# eink_schematic.net
KiCad netlist of a schematic drawn in EAGLE
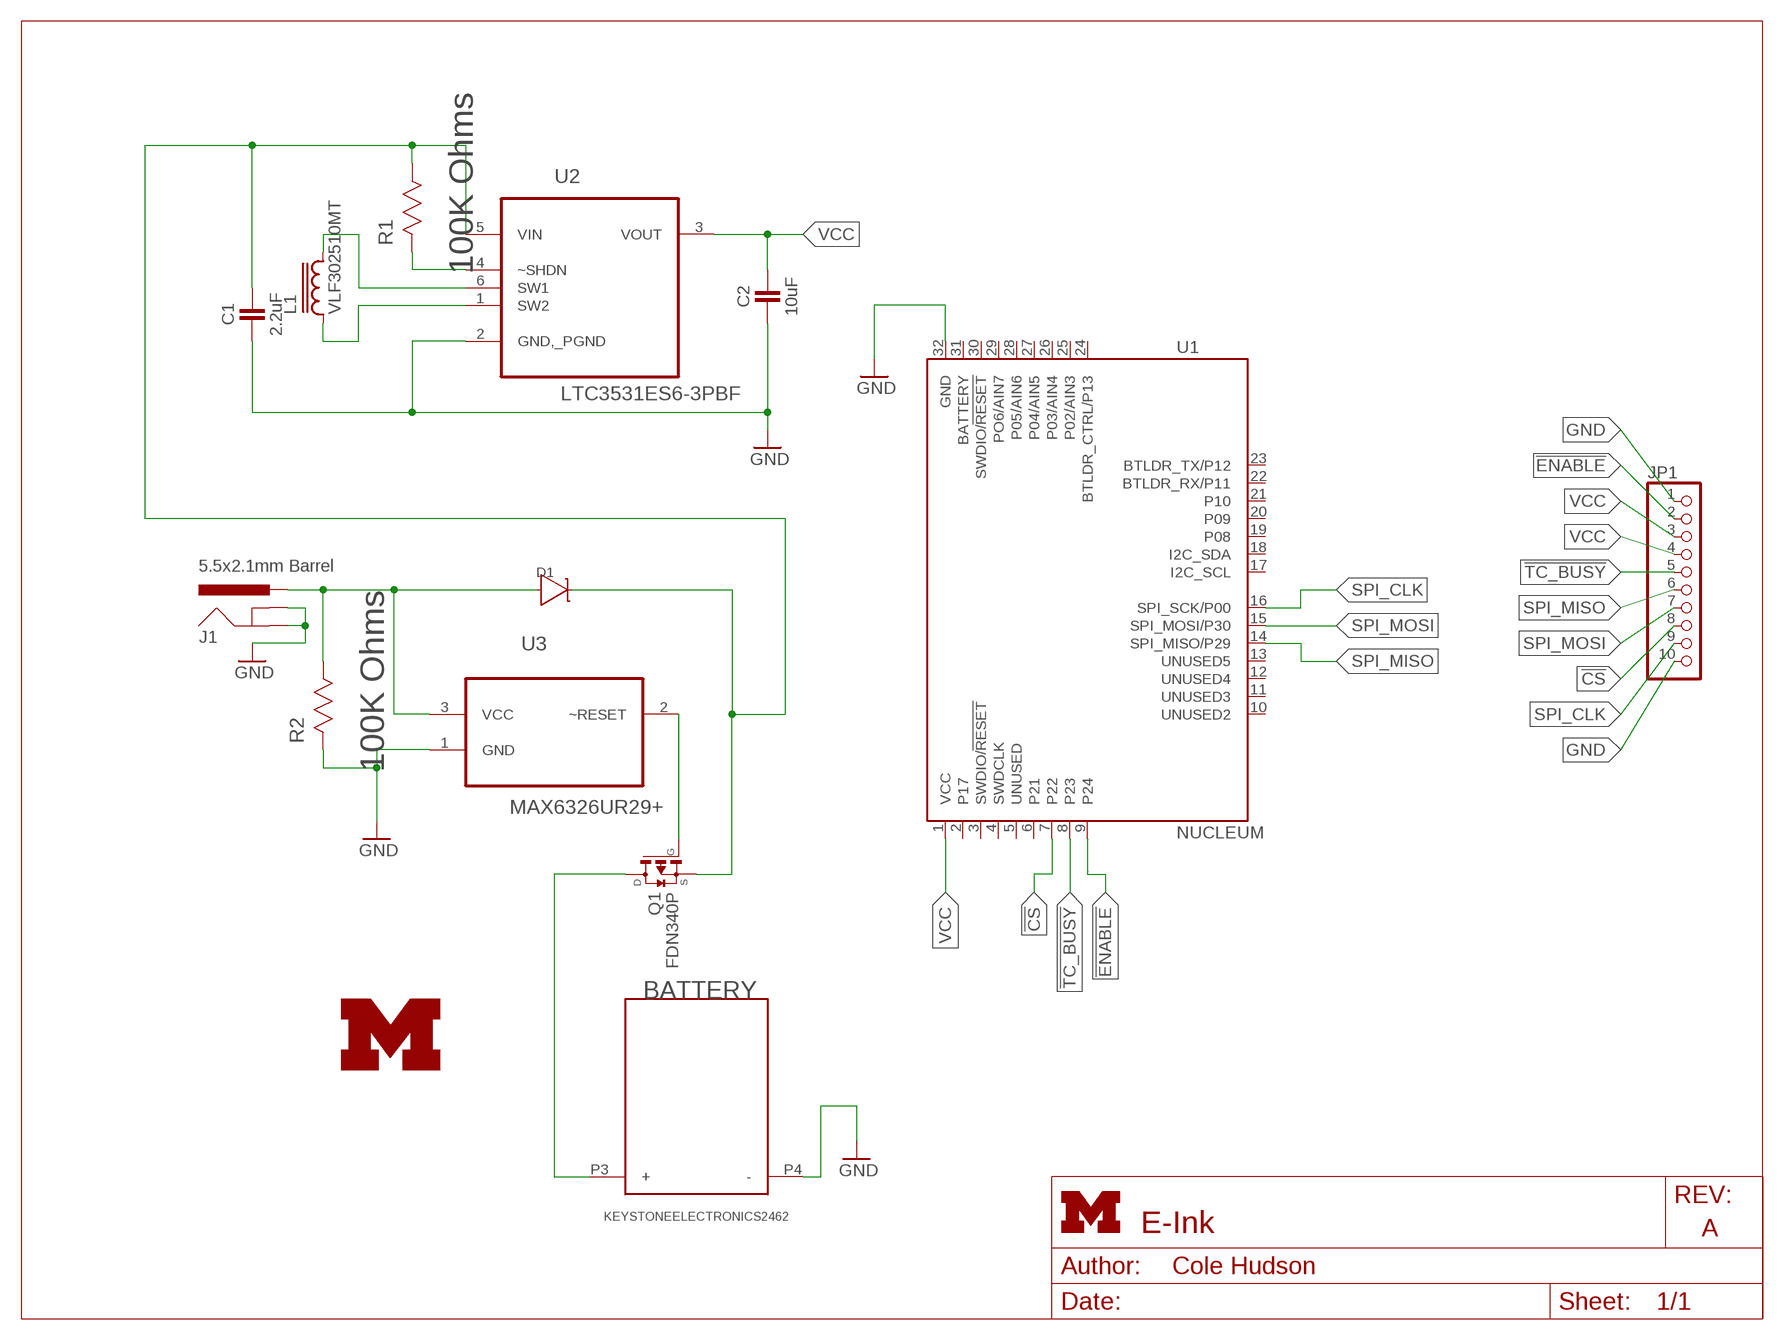
[diagram p0: schematic, sheet 1]

(export (version "E")
  (design (tool "Eeschema 10.0.6"))
  (components
    (comp (ref "BATTERY")
      (value "KEYSTONEELECTRONICS2462")
      (footprint "eagle-import:KEYSTONEELECTRONICS2462")
      (libsource (lib "eagle-import") (part "KEYSTONEELECTRONICS2462"))
    )
    (comp (ref "C1")
      (value "2.2uF")
      (footprint "eagle-import:0402_CAP")
      (libsource (lib "eagle-import") (part "CAPACITOR"))
    )
    (comp (ref "C2")
      (value "10uF")
      (footprint "eagle-import:0402_CAP")
      (libsource (lib "eagle-import") (part "CAPACITOR"))
    )
    (comp (ref "D1")
      (value "DIODE[SCHOTKY]-SOD123W")
      (footprint "eagle-import:SOD123W")
      (libsource (lib "eagle-import") (part "DIODE[SCHOTKY]-SOD123W"))
    )
    (comp (ref "J1")
      (value "5.5x2.1mm Barrel")
      (footprint "eagle-import:POWER_JACK_SMD")
      (libsource (lib "eagle-import") (part "POWER_JACKSMD"))
    )
    (comp (ref "JP1")
      (value "PINHD-1X10/90")
      (footprint "eagle-import:1X10_90")
      (libsource (lib "eagle-import") (part "PINHD-1X10/90"))
    )
    (comp (ref "L1")
      (value "VLF302510MT")
      (footprint "eagle-import:VLF302510MT")
      (libsource (lib "eagle-import") (part "VLF302510MT"))
    )
    (comp (ref "LOGO1")
      (value "UMICH_SOLID_LARGE")
      (footprint "eagle-import:UMICH_SOLID_350MIL")
      (libsource (lib "eagle-import") (part "UMICH_SOLID_LARGE"))
    )
    (comp (ref "Q1")
      (value "FDN340P")
      (footprint "eagle-import:SSOT-3")
      (libsource (lib "eagle-import") (part "FDN340P"))
    )
    (comp (ref "R1")
      (value "100K Ohms")
      (footprint "eagle-import:RESC1608X60N")
      (fields (field (name "MPN") "RC0603JR-07100KL") (field (name "TOLERANCE") "±5%"))
      (libsource (lib "eagle-import") (part "RC0603JR-07100KL"))
    )
    (comp (ref "R2")
      (value "100K Ohms")
      (footprint "eagle-import:RESC1608X60N")
      (fields (field (name "MPN") "RC0603JR-07100KL") (field (name "TOLERANCE") "±5%"))
      (libsource (lib "eagle-import") (part "RC0603JR-07100KL"))
    )
    (comp (ref "U1")
      (value "NUCLEUM")
      (footprint "eagle-import:NUCLEUM")
      (libsource (lib "eagle-import") (part "NUCLEUM"))
    )
    (comp (ref "U2")
      (value "LTC3531ES6-3PBF")
      (footprint "eagle-import:SOT95P280X100-6N")
      (fields (field (name "MPN") "LTC3531ES6-3#PBF"))
      (libsource (lib "eagle-import") (part "LTC3531ES6-3PBF"))
    )
    (comp (ref "U3")
      (value "MAX6326UR29+")
      (footprint "eagle-import:SOT95P228X119-3N")
      (libsource (lib "eagle-import") (part "MAX6326UR29+"))
    )
  )
  (nets
    (net (code "1") (name "/~{CS}") (class "Default")
      (node (ref "JP1") (pin "8") (pinfunction "8_8") (pintype "passive"))
      (node (ref "U1") (pin "7") (pinfunction "P22_7") (pintype "bidirectional"))
    )
    (net (code "2") (name "/~{ENABLE}") (class "Default")
      (node (ref "JP1") (pin "2") (pinfunction "2_2") (pintype "passive"))
      (node (ref "U1") (pin "9") (pinfunction "P24_9") (pintype "bidirectional"))
    )
    (net (code "3") (name "/~{TC_BUSY}") (class "Default")
      (node (ref "JP1") (pin "5") (pinfunction "5_5") (pintype "passive"))
      (node (ref "U1") (pin "8") (pinfunction "P23_8") (pintype "bidirectional"))
    )
    (net (code "4") (name "GND") (class "Default")
      (node (ref "BATTERY") (pin "P4") (pinfunction "-_P4") (pintype "bidirectional"))
      (node (ref "C1") (pin "2") (pinfunction "2_2") (pintype "bidirectional"))
      (node (ref "C2") (pin "2") (pinfunction "2_2") (pintype "bidirectional"))
      (node (ref "J1") (pin "GND") (pinfunction "GNDBREAK_GND") (pintype "bidirectional"))
      (node (ref "J1") (pin "P$4") (pinfunction "GND_P$4") (pintype "bidirectional"))
      (node (ref "JP1") (pin "1") (pinfunction "1_1") (pintype "passive"))
      (node (ref "JP1") (pin "10") (pinfunction "10_10") (pintype "passive"))
      (node (ref "R2") (pin "2") (pinfunction "R2_2") (pintype "passive"))
      (node (ref "U1") (pin "32") (pinfunction "GND_32") (pintype "bidirectional"))
      (node (ref "U2") (pin "2") (pinfunction "GND,_PGND_2") (pintype "passive"))
      (node (ref "U3") (pin "1") (pinfunction "GND_1") (pintype "passive"))
    )
    (net (code "5") (name "Net-(BATTERY-+)") (class "Default")
      (node (ref "BATTERY") (pin "P3") (pinfunction "+_P3") (pintype "bidirectional"))
      (node (ref "Q1") (pin "3") (pinfunction "D_3") (pintype "passive"))
    )
    (net (code "6") (name "Net-(D1-1)") (class "Default")
      (node (ref "D1") (pin "P$1") (pinfunction "1_P$1") (pintype "bidirectional"))
      (node (ref "J1") (pin "VIN0") (pinfunction "PWR_VIN0") (pintype "bidirectional"))
      (node (ref "R2") (pin "1") (pinfunction "R1_1") (pintype "passive"))
      (node (ref "U3") (pin "3") (pinfunction "VCC_3") (pintype "power_in"))
    )
    (net (code "7") (name "Net-(D1-2)") (class "Default")
      (node (ref "C1") (pin "1") (pinfunction "1_1") (pintype "bidirectional"))
      (node (ref "D1") (pin "P$2") (pinfunction "2_P$2") (pintype "bidirectional"))
      (node (ref "Q1") (pin "2") (pinfunction "S_2") (pintype "passive"))
      (node (ref "R1") (pin "1") (pinfunction "R1_1") (pintype "passive"))
      (node (ref "U2") (pin "5") (pinfunction "VIN_5") (pintype "power_in"))
    )
    (net (code "8") (name "Net-(Q1-G)") (class "Default")
      (node (ref "Q1") (pin "1") (pinfunction "G_1") (pintype "passive"))
      (node (ref "U3") (pin "2") (pinfunction "~{RESET}_2") (pintype "output"))
    )
    (net (code "9") (name "Net-(R1-R2)") (class "Default")
      (node (ref "R1") (pin "2") (pinfunction "R2_2") (pintype "passive"))
      (node (ref "U2") (pin "4") (pinfunction "~{SHDN}_4") (pintype "input"))
    )
    (net (code "10") (name "Net-(U2-SW1)") (class "Default")
      (node (ref "L1") (pin "2") (pinfunction "2_2") (pintype "passive"))
      (node (ref "U2") (pin "6") (pinfunction "SW1_6") (pintype "passive"))
    )
    (net (code "11") (name "Net-(U2-SW2)") (class "Default")
      (node (ref "L1") (pin "1") (pinfunction "1_1") (pintype "passive"))
      (node (ref "U2") (pin "1") (pinfunction "SW2_1") (pintype "passive"))
    )
    (net (code "12") (name "SPI_CLK") (class "Default")
      (node (ref "JP1") (pin "9") (pinfunction "9_9") (pintype "passive"))
      (node (ref "U1") (pin "16") (pinfunction "SPI_SCK/P00_16") (pintype "bidirectional"))
    )
    (net (code "13") (name "SPI_MISO") (class "Default")
      (node (ref "JP1") (pin "6") (pinfunction "6_6") (pintype "passive"))
      (node (ref "U1") (pin "14") (pinfunction "SPI_MISO/P29_14") (pintype "bidirectional"))
    )
    (net (code "14") (name "SPI_MOSI") (class "Default")
      (node (ref "JP1") (pin "7") (pinfunction "7_7") (pintype "passive"))
      (node (ref "U1") (pin "15") (pinfunction "SPI_MOSI/P30_15") (pintype "bidirectional"))
    )
    (net (code "15") (name "VCC") (class "Default")
      (node (ref "C2") (pin "1") (pinfunction "1_1") (pintype "bidirectional"))
      (node (ref "JP1") (pin "3") (pinfunction "3_3") (pintype "passive"))
      (node (ref "JP1") (pin "4") (pinfunction "4_4") (pintype "passive"))
      (node (ref "U1") (pin "1") (pinfunction "VCC_1") (pintype "bidirectional"))
      (node (ref "U2") (pin "3") (pinfunction "VOUT_3") (pintype "output"))
    )
    (net (code "16") (name "unconnected-(U1-BATTERY-Pad31)") (class "Default")
      (node (ref "U1") (pin "31") (pinfunction "BATTERY_31") (pintype "bidirectional"))
    )
    (net (code "17") (name "unconnected-(U1-BTLDR_CTRL{slash}P13-Pad24)") (class "Default")
      (node (ref "U1") (pin "24") (pinfunction "BTLDR_CTRL/P13_24") (pintype "bidirectional"))
    )
    (net (code "18") (name "unconnected-(U1-BTLDR_RX{slash}P11-Pad22)") (class "Default")
      (node (ref "U1") (pin "22") (pinfunction "BTLDR_RX/P11_22") (pintype "bidirectional"))
    )
    (net (code "19") (name "unconnected-(U1-BTLDR_TX{slash}P12-Pad23)") (class "Default")
      (node (ref "U1") (pin "23") (pinfunction "BTLDR_TX/P12_23") (pintype "bidirectional"))
    )
    (net (code "20") (name "unconnected-(U1-I2C_SCL-Pad17)") (class "Default")
      (node (ref "U1") (pin "17") (pinfunction "I2C_SCL_17") (pintype "bidirectional"))
    )
    (net (code "21") (name "unconnected-(U1-I2C_SDA-Pad18)") (class "Default")
      (node (ref "U1") (pin "18") (pinfunction "I2C_SDA_18") (pintype "bidirectional"))
    )
    (net (code "22") (name "unconnected-(U1-P02{slash}AIN3-Pad25)") (class "Default")
      (node (ref "U1") (pin "25") (pinfunction "P02/AIN3_25") (pintype "bidirectional"))
    )
    (net (code "23") (name "unconnected-(U1-P03{slash}AIN4-Pad26)") (class "Default")
      (node (ref "U1") (pin "26") (pinfunction "P03/AIN4_26") (pintype "bidirectional"))
    )
    (net (code "24") (name "unconnected-(U1-P04{slash}AIN5-Pad27)") (class "Default")
      (node (ref "U1") (pin "27") (pinfunction "P04/AIN5_27") (pintype "bidirectional"))
    )
    (net (code "25") (name "unconnected-(U1-P05{slash}AIN6-Pad28)") (class "Default")
      (node (ref "U1") (pin "28") (pinfunction "P05/AIN6_28") (pintype "bidirectional"))
    )
    (net (code "26") (name "unconnected-(U1-P08-Pad19)") (class "Default")
      (node (ref "U1") (pin "19") (pinfunction "P08_19") (pintype "bidirectional"))
    )
    (net (code "27") (name "unconnected-(U1-P09-Pad20)") (class "Default")
      (node (ref "U1") (pin "20") (pinfunction "P09_20") (pintype "bidirectional"))
    )
    (net (code "28") (name "unconnected-(U1-P10-Pad21)") (class "Default")
      (node (ref "U1") (pin "21") (pinfunction "P10_21") (pintype "bidirectional"))
    )
    (net (code "29") (name "unconnected-(U1-P17-Pad2)") (class "Default")
      (node (ref "U1") (pin "2") (pinfunction "P17_2") (pintype "bidirectional"))
    )
    (net (code "30") (name "unconnected-(U1-P21-Pad6)") (class "Default")
      (node (ref "U1") (pin "6") (pinfunction "P21_6") (pintype "bidirectional"))
    )
    (net (code "31") (name "unconnected-(U1-PO6{slash}AIN7-Pad29)") (class "Default")
      (node (ref "U1") (pin "29") (pinfunction "PO6/AIN7_29") (pintype "bidirectional"))
    )
    (net (code "32") (name "unconnected-(U1-SWDCLK-Pad4)") (class "Default")
      (node (ref "U1") (pin "4") (pinfunction "SWDCLK_4") (pintype "bidirectional"))
    )
    (net (code "33") (name "unconnected-(U1-SWDIO{slash}~{RESET}-Pad3)") (class "Default")
      (node (ref "U1") (pin "3") (pinfunction "SWDIO/~{RESET}_3") (pintype "bidirectional"))
    )
    (net (code "34") (name "unconnected-(U1-SWDIO{slash}~{RESET}-Pad30)") (class "Default")
      (node (ref "U1") (pin "30") (pinfunction "SWDIO/~{RESET}_30") (pintype "bidirectional"))
    )
    (net (code "35") (name "unconnected-(U1-UNUSED-Pad5)") (class "Default")
      (node (ref "U1") (pin "5") (pinfunction "UNUSED_5") (pintype "bidirectional"))
    )
    (net (code "36") (name "unconnected-(U1-UNUSED2-Pad10)") (class "Default")
      (node (ref "U1") (pin "10") (pinfunction "UNUSED2_10") (pintype "bidirectional"))
    )
    (net (code "37") (name "unconnected-(U1-UNUSED3-Pad11)") (class "Default")
      (node (ref "U1") (pin "11") (pinfunction "UNUSED3_11") (pintype "bidirectional"))
    )
    (net (code "38") (name "unconnected-(U1-UNUSED4-Pad12)") (class "Default")
      (node (ref "U1") (pin "12") (pinfunction "UNUSED4_12") (pintype "bidirectional"))
    )
    (net (code "39") (name "unconnected-(U1-UNUSED5-Pad13)") (class "Default")
      (node (ref "U1") (pin "13") (pinfunction "UNUSED5_13") (pintype "bidirectional"))
    )
  )
)
